# DigitalIO_3_3V_LevelShift.net
KiCad netlist of a schematic drawn in EAGLE
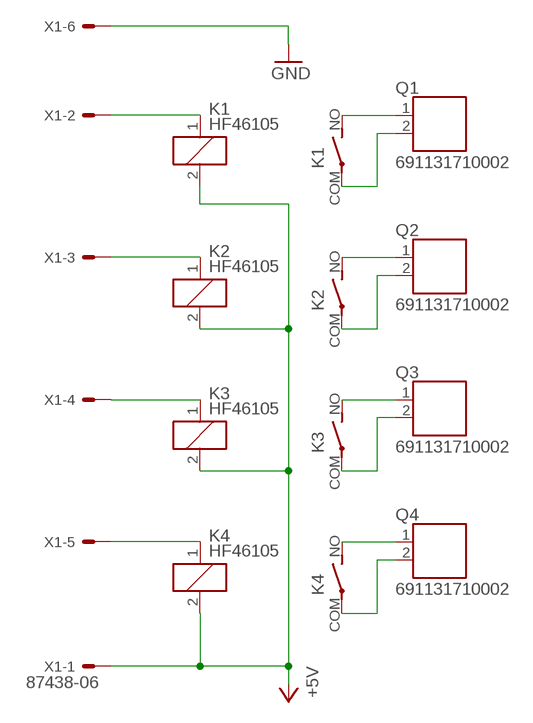
[diagram p0: schematic, sheet 1]

(export (version "E")
  (design (tool "Eeschema 10.0.6"))
  (components
    (comp (ref "K1")
      (value "HF46105")
      (footprint "eagle-import:HF46")
      (libsource (lib "eagle-import") (part "HF46?105"))
    )
    (comp (ref "K2")
      (value "HF46105")
      (footprint "eagle-import:HF46")
      (libsource (lib "eagle-import") (part "HF46?105"))
    )
    (comp (ref "K3")
      (value "HF46105")
      (footprint "eagle-import:HF46")
      (libsource (lib "eagle-import") (part "HF46?105"))
    )
    (comp (ref "K4")
      (value "HF46105")
      (footprint "eagle-import:HF46")
      (libsource (lib "eagle-import") (part "HF46?105"))
    )
    (comp (ref "Q1")
      (value "691131710002")
      (footprint "eagle-import:691131710002")
      (libsource (lib "eagle-import") (part "691131710002"))
    )
    (comp (ref "Q2")
      (value "691131710002")
      (footprint "eagle-import:691131710002")
      (libsource (lib "eagle-import") (part "691131710002"))
    )
    (comp (ref "Q3")
      (value "691131710002")
      (footprint "eagle-import:691131710002")
      (libsource (lib "eagle-import") (part "691131710002"))
    )
    (comp (ref "Q4")
      (value "691131710002")
      (footprint "eagle-import:691131710002")
      (libsource (lib "eagle-import") (part "691131710002"))
    )
    (comp (ref "X1")
      (value "87438-06")
      (footprint "eagle-import:87438-06")
      (fields (field (name "MPN") "87438-0643"))
      (libsource (lib "eagle-import") (part "87438-06"))
    )
  )
  (nets
    (net (code "1") (name "+5V") (class "Default")
      (node (ref "K1") (pin "2") (pinfunction "2_2") (pintype "passive"))
      (node (ref "K2") (pin "2") (pinfunction "2_2") (pintype "passive"))
      (node (ref "K3") (pin "2") (pinfunction "2_2") (pintype "passive"))
      (node (ref "K4") (pin "2") (pinfunction "2_2") (pintype "passive"))
      (node (ref "X1") (pin "1") (pinfunction "S_1") (pintype "passive"))
    )
    (net (code "2") (name "GND") (class "Default")
      (node (ref "X1") (pin "6") (pinfunction "S_6") (pintype "passive"))
    )
    (net (code "3") (name "Net-(K1B-P)") (class "Default")
      (node (ref "K1") (pin "COM") (pinfunction "P_COM") (pintype "passive"))
      (node (ref "Q1") (pin "2") (pinfunction "2_2") (pintype "passive"))
    )
    (net (code "4") (name "Net-(K1B-S)") (class "Default")
      (node (ref "K1") (pin "NO") (pinfunction "S_NO") (pintype "passive"))
      (node (ref "Q1") (pin "1") (pinfunction "1_1") (pintype "passive"))
    )
    (net (code "5") (name "Net-(K2B-P)") (class "Default")
      (node (ref "K2") (pin "COM") (pinfunction "P_COM") (pintype "passive"))
      (node (ref "Q2") (pin "2") (pinfunction "2_2") (pintype "passive"))
    )
    (net (code "6") (name "Net-(K2B-S)") (class "Default")
      (node (ref "K2") (pin "NO") (pinfunction "S_NO") (pintype "passive"))
      (node (ref "Q2") (pin "1") (pinfunction "1_1") (pintype "passive"))
    )
    (net (code "7") (name "Net-(K3B-P)") (class "Default")
      (node (ref "K3") (pin "COM") (pinfunction "P_COM") (pintype "passive"))
      (node (ref "Q3") (pin "2") (pinfunction "2_2") (pintype "passive"))
    )
    (net (code "8") (name "Net-(K3B-S)") (class "Default")
      (node (ref "K3") (pin "NO") (pinfunction "S_NO") (pintype "passive"))
      (node (ref "Q3") (pin "1") (pinfunction "1_1") (pintype "passive"))
    )
    (net (code "9") (name "Net-(K4B-P)") (class "Default")
      (node (ref "K4") (pin "COM") (pinfunction "P_COM") (pintype "passive"))
      (node (ref "Q4") (pin "2") (pinfunction "2_2") (pintype "passive"))
    )
    (net (code "10") (name "Net-(K4B-S)") (class "Default")
      (node (ref "K4") (pin "NO") (pinfunction "S_NO") (pintype "passive"))
      (node (ref "Q4") (pin "1") (pinfunction "1_1") (pintype "passive"))
    )
    (net (code "11") (name "Net-(X1B-S)") (class "Default")
      (node (ref "K1") (pin "1") (pinfunction "1_1") (pintype "passive"))
      (node (ref "X1") (pin "2") (pinfunction "S_2") (pintype "passive"))
    )
    (net (code "12") (name "Net-(X1C-S)") (class "Default")
      (node (ref "K2") (pin "1") (pinfunction "1_1") (pintype "passive"))
      (node (ref "X1") (pin "3") (pinfunction "S_3") (pintype "passive"))
    )
    (net (code "13") (name "Net-(X1D-S)") (class "Default")
      (node (ref "K3") (pin "1") (pinfunction "1_1") (pintype "passive"))
      (node (ref "X1") (pin "4") (pinfunction "S_4") (pintype "passive"))
    )
    (net (code "14") (name "Net-(X1E-S)") (class "Default")
      (node (ref "K4") (pin "1") (pinfunction "1_1") (pintype "passive"))
      (node (ref "X1") (pin "5") (pinfunction "S_5") (pintype "passive"))
    )
  )
)
